# Blaster.net
KiCad netlist of a schematic drawn in Altium Designer
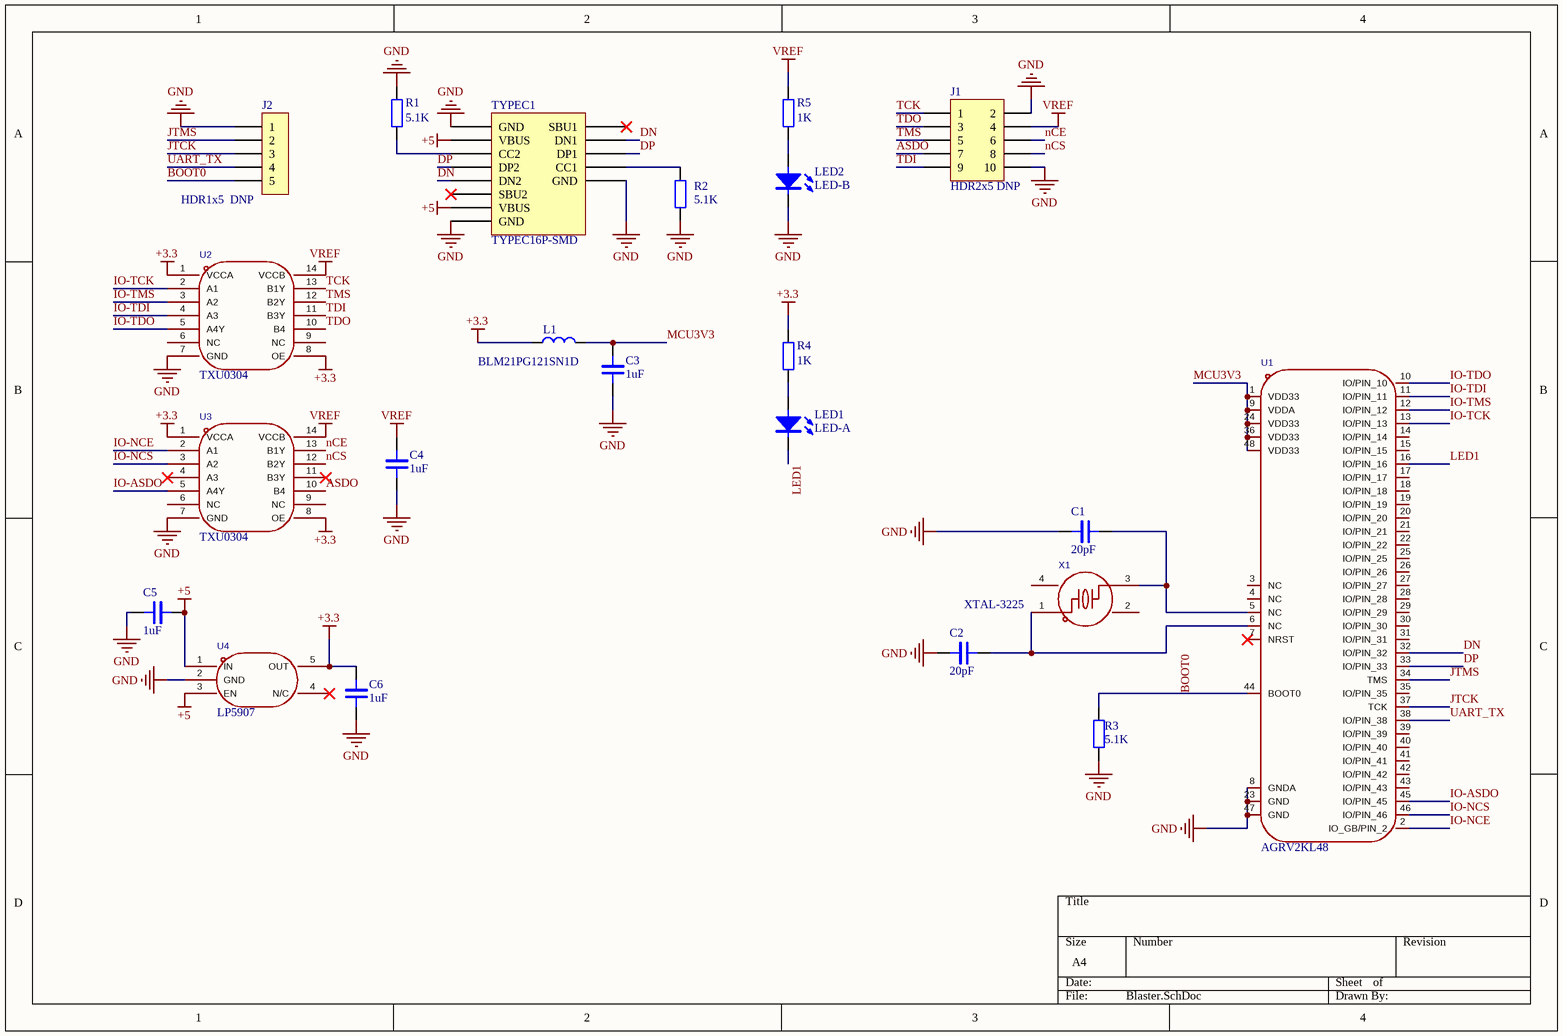
[diagram p0: Blaster.SchDoc]

(export (version "E")
  (design (tool "Eeschema 10.0.6"))
  (components
    (comp (ref "C1")
      (value "20pF")
      (footprint "LC-0603_C")
      (description "Capacitor")
      (libsource (lib "General") (part "CAP"))
    )
    (comp (ref "C2")
      (value "20pF")
      (footprint "LC-0603_C")
      (description "Capacitor")
      (libsource (lib "General") (part "CAP"))
    )
    (comp (ref "C3")
      (value "1uF")
      (footprint "LC-0603_C")
      (description "Capacitor")
      (libsource (lib "General") (part "CAP"))
    )
    (comp (ref "C4")
      (value "1uF")
      (footprint "LC-0603_C")
      (description "Capacitor")
      (libsource (lib "General") (part "CAP"))
    )
    (comp (ref "C5")
      (value "1uF")
      (footprint "LC-0603_C")
      (description "Capacitor")
      (libsource (lib "General") (part "CAP"))
    )
    (comp (ref "C6")
      (value "1uF")
      (footprint "LC-0603_C")
      (description "Capacitor")
      (libsource (lib "General") (part "CAP"))
    )
    (comp (ref "J1")
      (value "HDR2x5 DNP")
      (footprint "HDR-M-2.54_2X5_SMT")
      (description "Connector")
      (libsource (lib "General") (part "HDR2x5"))
    )
    (comp (ref "J2")
      (value "HDR1x5  DNP")
      (footprint "PIN-5-2.54-1.0")
      (libsource (lib "General") (part "HDR1x5"))
    )
    (comp (ref "L1")
      (value "BLM21PG121SN1D")
      (footprint "LC-0603_L")
      (description "Inductance")
      (libsource (lib "General") (part "INDUCTANCE"))
    )
    (comp (ref "LED1") (value "LED-A") (footprint "LED-0603") (libsource (lib "General") (part "LED")))
    (comp (ref "LED2")
      (value "LED-B")
      (footprint "LED-0603")
      (description "LED")
      (libsource (lib "General") (part "LED"))
    )
    (comp (ref "R1")
      (value "5.1K")
      (footprint "LC-0603_R")
      (description "Resistor")
      (libsource (lib "General") (part "RES"))
    )
    (comp (ref "R2") (value "5.1K") (footprint "LC-0603_R") (libsource (lib "") (part "RES_1")))
    (comp (ref "R3") (value "5.1K") (footprint "LC-0603_R") (libsource (lib "") (part "RES_1")))
    (comp (ref "R4")
      (value "1K")
      (footprint "LC-0603_R")
      (description "Resistor")
      (libsource (lib "General") (part "RES"))
    )
    (comp (ref "R5")
      (value "1K")
      (footprint "LC-0603_R")
      (description "Resistor")
      (libsource (lib "General") (part "RES"))
    )
    (comp (ref "TYPEC1")
      (value "TYPEC16P-SMD")
      (footprint "TYPE-C-Receptacle-2.0")
      (libsource (lib "General") (part "TYPEC16P-SMD"))
    )
    (comp (ref "U1")
      (value "AGRV2KL48")
      (footprint "LQFP48 7X7_N")
      (libsource (lib "General") (part "AGRV2KL48"))
    )
    (comp (ref "U2") (value "TXU0304") (footprint "TSSOP14_N") (libsource (lib "General") (part "TXU0304")))
    (comp (ref "U3") (value "TXU0304") (footprint "TSSOP14_N") (libsource (lib "General") (part "TXU0304")))
    (comp (ref "U4")
      (value "LP5907")
      (footprint "SOT23-5N")
      (libsource (lib "General") (part "LP5907MFX-3.3/NOPB"))
    )
    (comp (ref "X1") (value "XTAL-3225") (footprint "XTAL-3225") (libsource (lib "General") (part "XTAL-4P")))
  )
  (nets
    (net (code "1") (name "+3.3") (class "Default")
      (node (ref "C6") (pin "2") (pinfunction "2_2") (pintype "passive"))
      (node (ref "L1") (pin "1") (pinfunction "1_1") (pintype "passive"))
      (node (ref "R4") (pin "1") (pinfunction "1_1") (pintype "passive"))
      (node (ref "U2") (pin "1") (pinfunction "VCCA_1") (pintype "passive"))
      (node (ref "U2") (pin "8") (pinfunction "OE_8") (pintype "passive"))
      (node (ref "U3") (pin "1") (pinfunction "VCCA_1") (pintype "passive"))
      (node (ref "U3") (pin "8") (pinfunction "OE_8") (pintype "passive"))
      (node (ref "U4") (pin "5") (pinfunction "OUT_5") (pintype "passive"))
    )
    (net (code "2") (name "+5") (class "Default")
      (node (ref "C5") (pin "1") (pinfunction "1_1") (pintype "passive"))
      (node (ref "TYPEC1") (pin "A4") (pinfunction "VBUS_A4") (pintype "passive"))
      (node (ref "TYPEC1") (pin "B4") (pinfunction "VBUS_B4") (pintype "passive"))
      (node (ref "U4") (pin "1") (pinfunction "IN_1") (pintype "passive"))
      (node (ref "U4") (pin "3") (pinfunction "EN_3") (pintype "passive"))
    )
    (net (code "3") (name "/ASDO") (class "Default")
      (node (ref "J1") (pin "7") (pinfunction "7_7") (pintype "passive"))
      (node (ref "U3") (pin "10") (pinfunction "B4_10") (pintype "passive"))
    )
    (net (code "4") (name "/BOOT0") (class "Default")
      (node (ref "J2") (pin "5") (pinfunction "5_5") (pintype "passive"))
      (node (ref "R3") (pin "2") (pinfunction "2_2") (pintype "passive"))
      (node (ref "U1") (pin "44") (pinfunction "BOOT0_44") (pintype "passive"))
    )
    (net (code "5") (name "/DN") (class "Default")
      (node (ref "TYPEC1") (pin "A7") (pinfunction "DN1_A7") (pintype "passive"))
      (node (ref "TYPEC1") (pin "B7") (pinfunction "DN2_B7") (pintype "passive"))
      (node (ref "U1") (pin "32") (pinfunction "IO/PIN_32_32") (pintype "passive"))
    )
    (net (code "6") (name "/DP") (class "Default")
      (node (ref "TYPEC1") (pin "A6") (pinfunction "DP1_A6") (pintype "passive"))
      (node (ref "TYPEC1") (pin "B6") (pinfunction "DP2_B6") (pintype "passive"))
      (node (ref "U1") (pin "33") (pinfunction "IO/PIN_33_33") (pintype "passive"))
    )
    (net (code "7") (name "/IO-ASDO") (class "Default")
      (node (ref "U1") (pin "45") (pinfunction "IO/PIN_45_45") (pintype "passive"))
      (node (ref "U3") (pin "5") (pinfunction "A4Y_5") (pintype "passive"))
    )
    (net (code "8") (name "/IO-NCE") (class "Default")
      (node (ref "U1") (pin "2") (pinfunction "IO_GB/PIN_2_2") (pintype "passive"))
      (node (ref "U3") (pin "2") (pinfunction "A1_2") (pintype "passive"))
    )
    (net (code "9") (name "/IO-NCS") (class "Default")
      (node (ref "U1") (pin "46") (pinfunction "IO/PIN_46_46") (pintype "passive"))
      (node (ref "U3") (pin "3") (pinfunction "A2_3") (pintype "passive"))
    )
    (net (code "10") (name "/IO-TCK") (class "Default")
      (node (ref "U1") (pin "13") (pinfunction "IO/PIN_13_13") (pintype "passive"))
      (node (ref "U2") (pin "2") (pinfunction "A1_2") (pintype "passive"))
    )
    (net (code "11") (name "/IO-TDI") (class "Default")
      (node (ref "U1") (pin "11") (pinfunction "IO/PIN_11_11") (pintype "passive"))
      (node (ref "U2") (pin "4") (pinfunction "A3_4") (pintype "passive"))
    )
    (net (code "12") (name "/IO-TDO") (class "Default")
      (node (ref "U1") (pin "10") (pinfunction "IO/PIN_10_10") (pintype "passive"))
      (node (ref "U2") (pin "5") (pinfunction "A4Y_5") (pintype "passive"))
    )
    (net (code "13") (name "/IO-TMS") (class "Default")
      (node (ref "U1") (pin "12") (pinfunction "IO/PIN_12_12") (pintype "passive"))
      (node (ref "U2") (pin "3") (pinfunction "A2_3") (pintype "passive"))
    )
    (net (code "14") (name "/JTCK") (class "Default")
      (node (ref "J2") (pin "3") (pinfunction "3_3") (pintype "passive"))
      (node (ref "U1") (pin "37") (pinfunction "TCK_37") (pintype "passive"))
    )
    (net (code "15") (name "/JTMS") (class "Default")
      (node (ref "J2") (pin "2") (pinfunction "2_2") (pintype "passive"))
      (node (ref "U1") (pin "34") (pinfunction "TMS_34") (pintype "passive"))
    )
    (net (code "16") (name "/LED1") (class "Default")
      (node (ref "LED1") (pin "2") (pinfunction "C_2") (pintype "passive"))
      (node (ref "U1") (pin "16") (pinfunction "IO/PIN_16_16") (pintype "passive"))
    )
    (net (code "17") (name "/MCU3V3") (class "Default")
      (node (ref "C3") (pin "1") (pinfunction "1_1") (pintype "passive"))
      (node (ref "L1") (pin "2") (pinfunction "2_2") (pintype "passive"))
      (node (ref "U1") (pin "1") (pinfunction "VDD33_1") (pintype "passive"))
      (node (ref "U1") (pin "24") (pinfunction "VDD33_24") (pintype "passive"))
      (node (ref "U1") (pin "36") (pinfunction "VDD33_36") (pintype "passive"))
      (node (ref "U1") (pin "48") (pinfunction "VDD33_48") (pintype "passive"))
      (node (ref "U1") (pin "9") (pinfunction "VDDA_9") (pintype "passive"))
    )
    (net (code "18") (name "/TCK") (class "Default")
      (node (ref "J1") (pin "1") (pinfunction "1_1") (pintype "passive"))
      (node (ref "U2") (pin "13") (pinfunction "B1Y_13") (pintype "passive"))
    )
    (net (code "19") (name "/TDI") (class "Default")
      (node (ref "J1") (pin "9") (pinfunction "9_9") (pintype "passive"))
      (node (ref "U2") (pin "11") (pinfunction "B3Y_11") (pintype "passive"))
    )
    (net (code "20") (name "/TDO") (class "Default")
      (node (ref "J1") (pin "3") (pinfunction "3_3") (pintype "passive"))
      (node (ref "U2") (pin "10") (pinfunction "B4_10") (pintype "passive"))
    )
    (net (code "21") (name "/TMS") (class "Default")
      (node (ref "J1") (pin "5") (pinfunction "5_5") (pintype "passive"))
      (node (ref "U2") (pin "12") (pinfunction "B2Y_12") (pintype "passive"))
    )
    (net (code "22") (name "/UART_TX") (class "Default")
      (node (ref "J2") (pin "4") (pinfunction "4_4") (pintype "passive"))
      (node (ref "U1") (pin "38") (pinfunction "IO/PIN_38_38") (pintype "passive"))
    )
    (net (code "23") (name "/nCE") (class "Default")
      (node (ref "J1") (pin "6") (pinfunction "6_6") (pintype "passive"))
      (node (ref "U3") (pin "13") (pinfunction "B1Y_13") (pintype "passive"))
    )
    (net (code "24") (name "/nCS") (class "Default")
      (node (ref "J1") (pin "8") (pinfunction "8_8") (pintype "passive"))
      (node (ref "U3") (pin "12") (pinfunction "B2Y_12") (pintype "passive"))
    )
    (net (code "25") (name "GND") (class "Default")
      (node (ref "C1") (pin "2") (pinfunction "2_2") (pintype "passive"))
      (node (ref "C2") (pin "2") (pinfunction "2_2") (pintype "passive"))
      (node (ref "C3") (pin "2") (pinfunction "2_2") (pintype "passive"))
      (node (ref "C4") (pin "2") (pinfunction "2_2") (pintype "passive"))
      (node (ref "C5") (pin "2") (pinfunction "2_2") (pintype "passive"))
      (node (ref "C6") (pin "1") (pinfunction "1_1") (pintype "passive"))
      (node (ref "J1") (pin "10") (pinfunction "10_10") (pintype "passive"))
      (node (ref "J1") (pin "2") (pinfunction "2_2") (pintype "passive"))
      (node (ref "J2") (pin "1") (pinfunction "1_1") (pintype "passive"))
      (node (ref "LED2") (pin "2") (pinfunction "C_2") (pintype "passive"))
      (node (ref "R1") (pin "1") (pinfunction "1_1") (pintype "passive"))
      (node (ref "R2") (pin "1") (pinfunction "1_1") (pintype "passive"))
      (node (ref "R3") (pin "1") (pinfunction "1_1") (pintype "passive"))
      (node (ref "TYPEC1") (pin "0") (pinfunction "GND_0") (pintype "passive"))
      (node (ref "TYPEC1") (pin "A1") (pinfunction "GND_A1") (pintype "passive"))
      (node (ref "TYPEC1") (pin "B1") (pinfunction "GND_B1") (pintype "passive"))
      (node (ref "U1") (pin "23") (pinfunction "GND_23") (pintype "passive"))
      (node (ref "U1") (pin "47") (pinfunction "GND_47") (pintype "passive"))
      (node (ref "U1") (pin "8") (pinfunction "GNDA_8") (pintype "passive"))
      (node (ref "U2") (pin "7") (pinfunction "GND_7") (pintype "passive"))
      (node (ref "U3") (pin "7") (pinfunction "GND_7") (pintype "passive"))
      (node (ref "U4") (pin "2") (pinfunction "GND_2") (pintype "passive"))
    )
    (net (code "26") (name "Net-(C1-Pad1)") (class "Default")
      (node (ref "C1") (pin "1") (pinfunction "1_1") (pintype "passive"))
      (node (ref "U1") (pin "5") (pinfunction "NC_5") (pintype "passive"))
      (node (ref "X1") (pin "3") (pinfunction "3_3") (pintype "passive"))
    )
    (net (code "27") (name "Net-(C2-Pad1)") (class "Default")
      (node (ref "C2") (pin "1") (pinfunction "1_1") (pintype "passive"))
      (node (ref "U1") (pin "6") (pinfunction "NC_6") (pintype "passive"))
      (node (ref "X1") (pin "1") (pinfunction "1_1") (pintype "passive"))
    )
    (net (code "28") (name "Net-(LED1-A)") (class "Default")
      (node (ref "LED1") (pin "1") (pinfunction "A_1") (pintype "passive"))
      (node (ref "R4") (pin "2") (pinfunction "2_2") (pintype "passive"))
    )
    (net (code "29") (name "Net-(LED2-A)") (class "Default")
      (node (ref "LED2") (pin "1") (pinfunction "A_1") (pintype "passive"))
      (node (ref "R5") (pin "2") (pinfunction "2_2") (pintype "passive"))
    )
    (net (code "30") (name "Net-(TYPEC1-CC1)") (class "Default")
      (node (ref "R2") (pin "2") (pinfunction "2_2") (pintype "passive"))
      (node (ref "TYPEC1") (pin "A5") (pinfunction "CC1_A5") (pintype "passive"))
    )
    (net (code "31") (name "Net-(TYPEC1-CC2)") (class "Default")
      (node (ref "R1") (pin "2") (pinfunction "2_2") (pintype "passive"))
      (node (ref "TYPEC1") (pin "B5") (pinfunction "CC2_B5") (pintype "passive"))
    )
    (net (code "32") (name "VREF") (class "Default")
      (node (ref "C4") (pin "1") (pinfunction "1_1") (pintype "passive"))
      (node (ref "J1") (pin "4") (pinfunction "4_4") (pintype "passive"))
      (node (ref "R5") (pin "1") (pinfunction "1_1") (pintype "passive"))
      (node (ref "U2") (pin "14") (pinfunction "VCCB_14") (pintype "passive"))
      (node (ref "U3") (pin "14") (pinfunction "VCCB_14") (pintype "passive"))
    )
    (net (code "33") (name "unconnected-(TYPEC1-SBU1-PadA8)") (class "Default")
      (node (ref "TYPEC1") (pin "A8") (pinfunction "SBU1_A8") (pintype "passive+no_connect"))
    )
    (net (code "34") (name "unconnected-(TYPEC1-SBU2-PadB8)") (class "Default")
      (node (ref "TYPEC1") (pin "B8") (pinfunction "SBU2_B8") (pintype "passive+no_connect"))
    )
    (net (code "35") (name "unconnected-(U1-IO{slash}PIN_14-Pad14)") (class "Default")
      (node (ref "U1") (pin "14") (pinfunction "IO/PIN_14_14") (pintype "passive"))
    )
    (net (code "36") (name "unconnected-(U1-IO{slash}PIN_15-Pad15)") (class "Default")
      (node (ref "U1") (pin "15") (pinfunction "IO/PIN_15_15") (pintype "passive"))
    )
    (net (code "37") (name "unconnected-(U1-IO{slash}PIN_17-Pad17)") (class "Default")
      (node (ref "U1") (pin "17") (pinfunction "IO/PIN_17_17") (pintype "passive"))
    )
    (net (code "38") (name "unconnected-(U1-IO{slash}PIN_18-Pad18)") (class "Default")
      (node (ref "U1") (pin "18") (pinfunction "IO/PIN_18_18") (pintype "passive"))
    )
    (net (code "39") (name "unconnected-(U1-IO{slash}PIN_19-Pad19)") (class "Default")
      (node (ref "U1") (pin "19") (pinfunction "IO/PIN_19_19") (pintype "passive"))
    )
    (net (code "40") (name "unconnected-(U1-IO{slash}PIN_20-Pad20)") (class "Default")
      (node (ref "U1") (pin "20") (pinfunction "IO/PIN_20_20") (pintype "passive"))
    )
    (net (code "41") (name "unconnected-(U1-IO{slash}PIN_21-Pad21)") (class "Default")
      (node (ref "U1") (pin "21") (pinfunction "IO/PIN_21_21") (pintype "passive"))
    )
    (net (code "42") (name "unconnected-(U1-IO{slash}PIN_22-Pad22)") (class "Default")
      (node (ref "U1") (pin "22") (pinfunction "IO/PIN_22_22") (pintype "passive"))
    )
    (net (code "43") (name "unconnected-(U1-IO{slash}PIN_25-Pad25)") (class "Default")
      (node (ref "U1") (pin "25") (pinfunction "IO/PIN_25_25") (pintype "passive"))
    )
    (net (code "44") (name "unconnected-(U1-IO{slash}PIN_26-Pad26)") (class "Default")
      (node (ref "U1") (pin "26") (pinfunction "IO/PIN_26_26") (pintype "passive"))
    )
    (net (code "45") (name "unconnected-(U1-IO{slash}PIN_27-Pad27)") (class "Default")
      (node (ref "U1") (pin "27") (pinfunction "IO/PIN_27_27") (pintype "passive"))
    )
    (net (code "46") (name "unconnected-(U1-IO{slash}PIN_28-Pad28)") (class "Default")
      (node (ref "U1") (pin "28") (pinfunction "IO/PIN_28_28") (pintype "passive"))
    )
    (net (code "47") (name "unconnected-(U1-IO{slash}PIN_29-Pad29)") (class "Default")
      (node (ref "U1") (pin "29") (pinfunction "IO/PIN_29_29") (pintype "passive"))
    )
    (net (code "48") (name "unconnected-(U1-IO{slash}PIN_30-Pad30)") (class "Default")
      (node (ref "U1") (pin "30") (pinfunction "IO/PIN_30_30") (pintype "passive"))
    )
    (net (code "49") (name "unconnected-(U1-IO{slash}PIN_31-Pad31)") (class "Default")
      (node (ref "U1") (pin "31") (pinfunction "IO/PIN_31_31") (pintype "passive"))
    )
    (net (code "50") (name "unconnected-(U1-IO{slash}PIN_35-Pad35)") (class "Default")
      (node (ref "U1") (pin "35") (pinfunction "IO/PIN_35_35") (pintype "passive"))
    )
    (net (code "51") (name "unconnected-(U1-IO{slash}PIN_39-Pad39)") (class "Default")
      (node (ref "U1") (pin "39") (pinfunction "IO/PIN_39_39") (pintype "passive"))
    )
    (net (code "52") (name "unconnected-(U1-IO{slash}PIN_40-Pad40)") (class "Default")
      (node (ref "U1") (pin "40") (pinfunction "IO/PIN_40_40") (pintype "passive"))
    )
    (net (code "53") (name "unconnected-(U1-IO{slash}PIN_41-Pad41)") (class "Default")
      (node (ref "U1") (pin "41") (pinfunction "IO/PIN_41_41") (pintype "passive"))
    )
    (net (code "54") (name "unconnected-(U1-IO{slash}PIN_42-Pad42)") (class "Default")
      (node (ref "U1") (pin "42") (pinfunction "IO/PIN_42_42") (pintype "passive"))
    )
    (net (code "55") (name "unconnected-(U1-IO{slash}PIN_43-Pad43)") (class "Default")
      (node (ref "U1") (pin "43") (pinfunction "IO/PIN_43_43") (pintype "passive"))
    )
    (net (code "56") (name "unconnected-(U1-NC-Pad3)") (class "Default")
      (node (ref "U1") (pin "3") (pinfunction "NC_3") (pintype "passive"))
    )
    (net (code "57") (name "unconnected-(U1-NC-Pad4)") (class "Default")
      (node (ref "U1") (pin "4") (pinfunction "NC_4") (pintype "passive"))
    )
    (net (code "58") (name "unconnected-(U1-NRST-Pad7)") (class "Default")
      (node (ref "U1") (pin "7") (pinfunction "NRST_7") (pintype "passive+no_connect"))
    )
    (net (code "59") (name "unconnected-(U2-NC-Pad6)") (class "Default")
      (node (ref "U2") (pin "6") (pinfunction "NC_6") (pintype "passive"))
    )
    (net (code "60") (name "unconnected-(U2-NC-Pad9)") (class "Default")
      (node (ref "U2") (pin "9") (pinfunction "NC_9") (pintype "passive"))
    )
    (net (code "61") (name "unconnected-(U3-A3-Pad4)") (class "Default")
      (node (ref "U3") (pin "4") (pinfunction "A3_4") (pintype "passive+no_connect"))
    )
    (net (code "62") (name "unconnected-(U3-B3Y-Pad11)") (class "Default")
      (node (ref "U3") (pin "11") (pinfunction "B3Y_11") (pintype "passive+no_connect"))
    )
    (net (code "63") (name "unconnected-(U3-NC-Pad6)") (class "Default")
      (node (ref "U3") (pin "6") (pinfunction "NC_6") (pintype "passive"))
    )
    (net (code "64") (name "unconnected-(U3-NC-Pad9)") (class "Default")
      (node (ref "U3") (pin "9") (pinfunction "NC_9") (pintype "passive"))
    )
    (net (code "65") (name "unconnected-(U4-N{slash}C-Pad4)") (class "Default")
      (node (ref "U4") (pin "4") (pinfunction "N/C_4") (pintype "passive+no_connect"))
    )
    (net (code "66") (name "unconnected-(X1-GND-Pad2)") (class "Default")
      (node (ref "X1") (pin "2") (pinfunction "GND_2") (pintype "passive"))
    )
    (net (code "67") (name "unconnected-(X1-GND-Pad4)") (class "Default")
      (node (ref "X1") (pin "4") (pinfunction "GND_4") (pintype "passive"))
    )
  )
)
